# 09-WIFI.net
KiCad netlist of a schematic drawn in Altium Designer
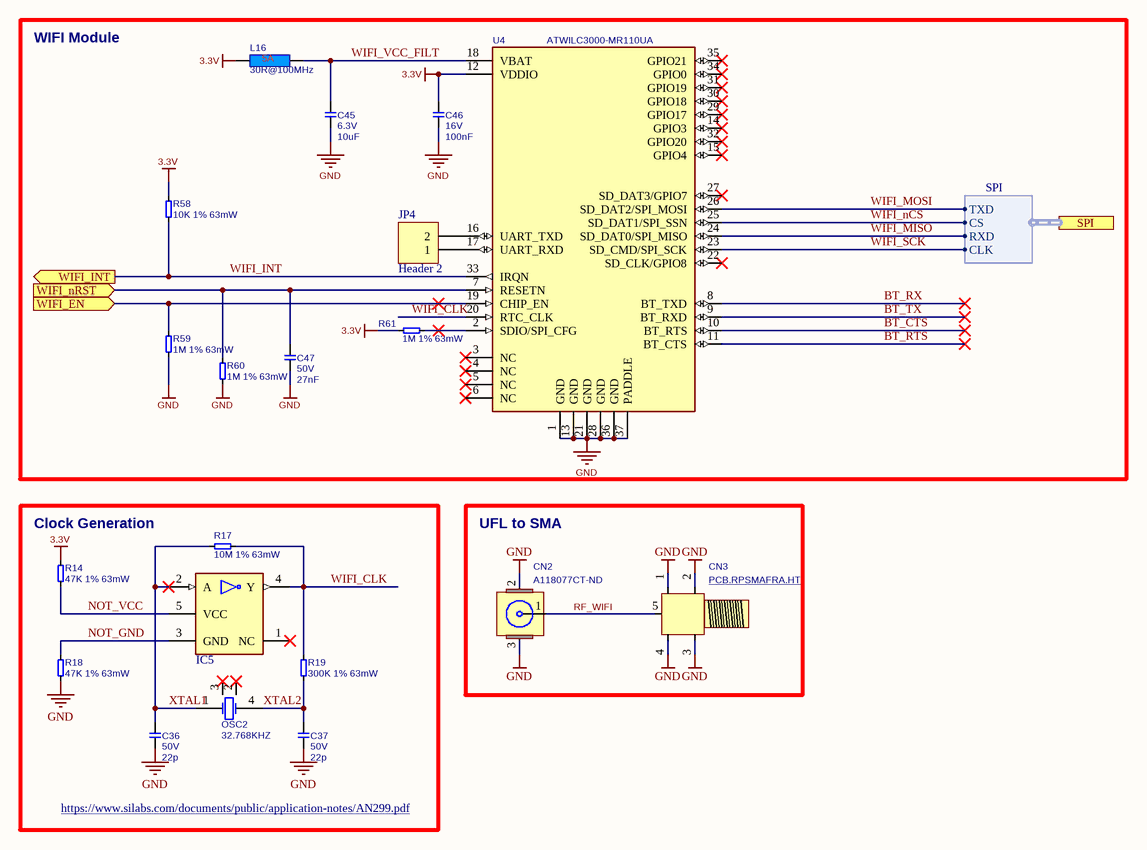
[diagram p0: 09-WIFI.SchDoc]

(export (version "E")
  (design (tool "Eeschema 10.0.6"))
  (components
    (comp (ref "C36")
      (value "22p")
      (footprint "T_CAPC0603X33N")
      (description "Capacitor Ceramic C0G 22pF 50V 10% 0603")
      (fields
        (field (name "TOLERANCE") "10%")
        (field (name "RATING") "50V")
        (field (name "Comment") "22pF 50V 10% C0G")
      )
      (libsource (lib "AI Gateway - Carrier") (part "C-22pF-50V-10%-0603"))
    )
    (comp (ref "C37")
      (value "22p")
      (footprint "T_CAPC0603X33N")
      (description "Capacitor Ceramic C0G 22pF 50V 10% 0603")
      (fields
        (field (name "TOLERANCE") "10%")
        (field (name "RATING") "50V")
        (field (name "Comment") "22pF 50V 10% C0G")
      )
      (libsource (lib "AI Gateway - Carrier") (part "C-22pF-50V-10%-0603"))
    )
    (comp (ref "C45")
      (value "10uF")
      (footprint "T_CAPC0603X33N")
      (description "Capacitor Ceramic X5R 10uF 6.3V 20% 0603")
      (fields
        (field (name "TOLERANCE") "20%")
        (field (name "RATING") "6.3V")
        (field (name "Comment") "10uF 6.3V 20% X5R")
      )
      (libsource (lib "AI Gateway - Carrier") (part "C-10uF-6.3V-20%-0603"))
    )
    (comp (ref "C46")
      (value "100nF")
      (footprint "CAPC1005X60N")
      (description "Capacitor Ceramic X7R 100nF 16V 10% 0603")
      (fields
        (field (name "TOLERANCE") "10%")
        (field (name "RATING") "16V")
        (field (name "Comment") "100nF 16V 10% X7R")
      )
      (libsource (lib "AI Gateway - Carrier") (part "C-100nF-16V-10%-0603"))
    )
    (comp (ref "C47")
      (value "27nF")
      (footprint "T_CAPC0603X33N")
      (description "Capacitor Ceramic X7R 27nF 50V 10% 0603")
      (fields
        (field (name "TOLERANCE") "10%")
        (field (name "RATING") "50V")
        (field (name "Comment") "27nF 50V 20% X7R")
      )
      (libsource (lib "AI Gateway - Carrier") (part "C-27nF-50V-10%-0603"))
    )
    (comp (ref "CN2")
      (value "A118077CT-ND")
      (footprint "U.FL-R-SMT-1")
      (description "U.FL (UMCC) Connector Jack, Male Pin 50Ohm Surface Mount Solder")
      (fields
        (field (name "MFG") "TE Connectivity AMP Connectors")
        (field (name "FOOTPRINT CHECKED") "Assign OK, Footprint OK")
      )
      (libsource (lib "Connectors") (part "CON-TE-A118077CT-ND"))
    )
    (comp (ref "CN3")
      (value "PCB.RPSMAFRA.HT")
      (footprint "0733910320")
      (description "RP-SMA Conector Jack, clavija macho 50Ohm Orificio pasante, ángulo recto Soldadura")
      (fields
        (field (name "MFG") "Taoglas Limited")
        (field (name "FOOTPRINT CHECKED") "Assign OK, Footprint OK")
      )
      (libsource (lib "Connectors") (part "CON-Taoglas-PCB.RPSMAFRA.HT"))
    )
    (comp (ref "IC5")
      (value "SN74LVC1G04")
      (footprint "SOT65P210X110-5N")
      (description "IC INVERTER 1CH 1-INP SC70-5")
      (fields (field (name "MFG") "Texas Instruments"))
      (libsource (lib "AIGateway") (part "IC-TI-SN74LVC1G04"))
    )
    (comp (ref "JP4")
      (value "Header 2")
      (footprint "HDR1X2")
      (description "Header, 2-Pin")
      (fields (field (name "PUBLISHER") "Altium Limited"))
      (libsource (lib "Miscellaneous Connectors") (part "Header 2"))
    )
    (comp (ref "L16")
      (value "30R@100MHz")
      (footprint "INDC1608X95N")
      (description "30 Ohms @ 100MHz 1 Power Line Ferrite Bead 0603 (1608 Metric) 5A 10mOhm")
      (fields
        (field (name "TOLERANCE") "25%")
        (field (name "MFG") "EXC-ML20A390U")
        (field (name "FOOTPRINT CHECKED") "Ok, Assign Ok")
      )
      (libsource (lib "Passive") (part "L-Murata-30R@100MHz-5A-0603"))
    )
    (comp (ref "OSC2")
      (value "32.768KHZ")
      (footprint "OSC_ABRACON_ABS25")
      (description "32.768kHz ±20ppm Cristal 12.5pF  4-SOJ, 5.50mm step")
      (fields (field (name "TOLERANCE") "20ppm") (field (name "MFG") "ABRACON"))
      (libsource (lib "Passive") (part "OSC-ABS25-32.768KHZ-T"))
    )
    (comp (ref "R14")
      (value "47K 1% 63mW")
      (footprint "RESC1005X40N")
      (description "Resistor 47Kohm 63mW 1% 0402")
      (fields (field (name "POWER") "63mW") (field (name "TOLERANCE") "1%"))
      (libsource (lib "AI Gateway - Carrier") (part "R-47K-1%-0402"))
    )
    (comp (ref "R17")
      (value "10M 1% 63mW")
      (footprint "RESC1005X40N")
      (description "Resistor 10Mohm 63mW 1% 0402")
      (fields (field (name "POWER") "63mW") (field (name "TOLERANCE") "1%"))
      (libsource (lib "AI Gateway - Carrier") (part "R-10M-1%-0402"))
    )
    (comp (ref "R18")
      (value "47K 1% 63mW")
      (footprint "RESC1005X40N")
      (description "Resistor 47Kohm 63mW 1% 0402")
      (fields (field (name "POWER") "63mW") (field (name "TOLERANCE") "1%"))
      (libsource (lib "AI Gateway - Carrier") (part "R-47K-1%-0402"))
    )
    (comp (ref "R19")
      (value "300K 1% 63mW")
      (footprint "RESC1005X40N")
      (description "Resistor 300Kohm 63mW 1% 0402")
      (fields (field (name "POWER") "63mW") (field (name "TOLERANCE") "1%"))
      (libsource (lib "AI Gateway - Carrier") (part "R-300K-1%-0402"))
    )
    (comp (ref "R58")
      (value "10K 1% 63mW")
      (footprint "RESC1005X40N")
      (description "Resistor 10Kohm 63mW 1% 0402")
      (fields (field (name "POWER") "63mW") (field (name "TOLERANCE") "1%"))
      (libsource (lib "AI Gateway - Carrier") (part "R-10K-1%-0402"))
    )
    (comp (ref "R59")
      (value "1M 1% 63mW")
      (footprint "RESC1005X40N")
      (description "Resistor 1Mohm 63mW 1% 0402")
      (fields (field (name "POWER") "63mW") (field (name "TOLERANCE") "1%"))
      (libsource (lib "AI Gateway - Carrier") (part "R-1M-1%-0402"))
    )
    (comp (ref "R60")
      (value "1M 1% 63mW")
      (footprint "RESC1005X40N")
      (description "Resistor 1Mohm 63mW 1% 0402")
      (fields (field (name "POWER") "63mW") (field (name "TOLERANCE") "1%"))
      (libsource (lib "AI Gateway - Carrier") (part "R-1M-1%-0402"))
    )
    (comp (ref "R61")
      (value "1M 1% 63mW")
      (footprint "RESC1005X40N")
      (description "Resistor 1Mohm 63mW 1% 0402")
      (fields (field (name "POWER") "63mW") (field (name "TOLERANCE") "1%"))
      (libsource (lib "AI Gateway - Carrier") (part "R-1M-1%-0402"))
    )
    (comp (ref "U4")
      (value "ATWILC3000-MR110UA")
      (footprint "AIGateway:ATWILC3000-MR110CA")
      (fields (field (name "MFG") "MICROCHIP") (field (name "SYMBOL CHECKED") "M"))
      (libsource (lib "AIGateway") (part "IC-Microchip-ATWILC3000"))
    )
  )
  (nets
    (net (code "2") (name "/BT_CTS") (class "Default")
      (node (ref "U4") (pin "10") (pinfunction "BT_RTS_10") (pintype "bidirectional+no_connect"))
    )
    (net (code "3") (name "/BT_RTS") (class "Default")
      (node (ref "U4") (pin "11") (pinfunction "BT_CTS_11") (pintype "bidirectional+no_connect"))
    )
    (net (code "4") (name "/BT_RX") (class "Default")
      (node (ref "U4") (pin "8") (pinfunction "BT_TXD_8") (pintype "bidirectional+no_connect"))
    )
    (net (code "5") (name "/BT_TX") (class "Default")
      (node (ref "U4") (pin "9") (pinfunction "BT_RXD_9") (pintype "bidirectional+no_connect"))
    )
    (net (code "6") (name "/NOT_GND") (class "Default")
      (node (ref "IC5") (pin "3") (pinfunction "GND_3") (pintype "power_in"))
      (node (ref "R18") (pin "2") (pinfunction "2_2") (pintype "passive"))
    )
    (net (code "7") (name "/NOT_VCC") (class "Default")
      (node (ref "IC5") (pin "5") (pinfunction "VCC_5") (pintype "power_in"))
      (node (ref "R14") (pin "1") (pinfunction "1_1") (pintype "passive"))
    )
    (net (code "8") (name "/RF_WIFI") (class "Default")
      (node (ref "CN2") (pin "1") (pinfunction "SIG_1") (pintype "passive"))
      (node (ref "CN3") (pin "5") (pinfunction "SIG_5") (pintype "passive"))
    )
    (net (code "9") (name "/WIFI_CLK") (class "Default")
      (node (ref "IC5") (pin "4") (pinfunction "Y_4") (pintype "output"))
      (node (ref "R17") (pin "1") (pinfunction "1_1") (pintype "passive"))
      (node (ref "R19") (pin "2") (pinfunction "2_2") (pintype "passive"))
      (node (ref "U4") (pin "20") (pinfunction "RTC_CLK_20") (pintype "input"))
    )
    (net (code "10") (name "/WIFI_EN") (class "Default")
      (node (ref "R59") (pin "2") (pinfunction "2_2") (pintype "passive"))
      (node (ref "U4") (pin "19") (pinfunction "CHIP_EN_19") (pintype "input"))
    )
    (net (code "11") (name "/WIFI_INT") (class "Default")
      (node (ref "R58") (pin "1") (pinfunction "1_1") (pintype "passive"))
      (node (ref "U4") (pin "33") (pinfunction "IRQN_33") (pintype "output"))
    )
    (net (code "12") (name "/WIFI_MISO") (class "Default")
      (node (ref "U4") (pin "24") (pinfunction "SD_DAT0/SPI_MISO_24") (pintype "bidirectional"))
    )
    (net (code "13") (name "/WIFI_MOSI") (class "Default")
      (node (ref "U4") (pin "26") (pinfunction "SD_DAT2/SPI_MOSI_26") (pintype "bidirectional"))
    )
    (net (code "14") (name "/WIFI_SCK") (class "Default")
      (node (ref "U4") (pin "23") (pinfunction "SD_CMD/SPI_SCK_23") (pintype "bidirectional"))
    )
    (net (code "15") (name "/WIFI_VCC_FILT") (class "Default")
      (node (ref "C45") (pin "2") (pinfunction "2_2") (pintype "passive"))
      (node (ref "L16") (pin "1") (pinfunction "1_1") (pintype "passive"))
      (node (ref "U4") (pin "18") (pinfunction "VBAT_18") (pintype "power_in"))
    )
    (net (code "16") (name "/WIFI_nCS") (class "Default")
      (node (ref "U4") (pin "25") (pinfunction "SD_DAT1/SPI_SSN_25") (pintype "bidirectional"))
    )
    (net (code "17") (name "/WIFI_nRST") (class "Default")
      (node (ref "C47") (pin "2") (pinfunction "2_2") (pintype "passive"))
      (node (ref "R60") (pin "2") (pinfunction "2_2") (pintype "passive"))
      (node (ref "U4") (pin "7") (pinfunction "RESETN_7") (pintype "input"))
    )
    (net (code "18") (name "/XTAL1") (class "Default")
      (node (ref "C36") (pin "2") (pinfunction "2_2") (pintype "passive"))
      (node (ref "IC5") (pin "2") (pinfunction "A_2") (pintype "input"))
      (node (ref "OSC2") (pin "1") (pinfunction "OSC1_1") (pintype "passive"))
      (node (ref "R17") (pin "2") (pinfunction "2_2") (pintype "passive"))
    )
    (net (code "19") (name "/XTAL2") (class "Default")
      (node (ref "C37") (pin "2") (pinfunction "2_2") (pintype "passive"))
      (node (ref "OSC2") (pin "4") (pinfunction "OSC4_4") (pintype "passive"))
      (node (ref "R19") (pin "1") (pinfunction "1_1") (pintype "passive"))
    )
    (net (code "21") (name "3.3V") (class "Default")
      (node (ref "C46") (pin "2") (pinfunction "2_2") (pintype "passive"))
      (node (ref "L16") (pin "2") (pinfunction "2_2") (pintype "passive"))
      (node (ref "R14") (pin "2") (pinfunction "2_2") (pintype "passive"))
      (node (ref "R58") (pin "2") (pinfunction "2_2") (pintype "passive"))
      (node (ref "R61") (pin "1") (pinfunction "1_1") (pintype "passive"))
      (node (ref "U4") (pin "12") (pinfunction "VDDIO_12") (pintype "power_in"))
    )
    (net (code "22") (name "GND") (class "Default")
      (node (ref "C36") (pin "1") (pinfunction "1_1") (pintype "passive"))
      (node (ref "C37") (pin "1") (pinfunction "1_1") (pintype "passive"))
      (node (ref "C45") (pin "1") (pinfunction "1_1") (pintype "passive"))
      (node (ref "C46") (pin "1") (pinfunction "1_1") (pintype "passive"))
      (node (ref "C47") (pin "1") (pinfunction "1_1") (pintype "passive"))
      (node (ref "CN2") (pin "2") (pinfunction "GND_2") (pintype "passive"))
      (node (ref "CN2") (pin "3") (pinfunction "GND_3") (pintype "passive"))
      (node (ref "CN3") (pin "1") (pinfunction "GND_1") (pintype "passive"))
      (node (ref "CN3") (pin "2") (pinfunction "GND_2") (pintype "passive"))
      (node (ref "CN3") (pin "3") (pinfunction "GND_3") (pintype "passive"))
      (node (ref "CN3") (pin "4") (pinfunction "GND_4") (pintype "passive"))
      (node (ref "R18") (pin "1") (pinfunction "1_1") (pintype "passive"))
      (node (ref "R59") (pin "1") (pinfunction "1_1") (pintype "passive"))
      (node (ref "R60") (pin "1") (pinfunction "1_1") (pintype "passive"))
      (node (ref "U4") (pin "1") (pinfunction "GND_1") (pintype "power_in"))
      (node (ref "U4") (pin "13") (pinfunction "GND_13") (pintype "power_in"))
      (node (ref "U4") (pin "21") (pinfunction "GND_21") (pintype "power_in"))
      (node (ref "U4") (pin "28") (pinfunction "GND_28") (pintype "power_in"))
      (node (ref "U4") (pin "36") (pinfunction "GND_36") (pintype "power_in"))
      (node (ref "U4") (pin "37") (pinfunction "PADDLE_37") (pintype "power_in"))
    )
    (net (code "23") (name "Net-(U4-SDIO{slash}SPI_CFG)") (class "Default")
      (node (ref "R61") (pin "2") (pinfunction "2_2") (pintype "passive"))
      (node (ref "U4") (pin "2") (pinfunction "SDIO/SPI_CFG_2") (pintype "input"))
    )
    (net (code "24") (name "Net-(U4-UART_RXD)") (class "Default")
      (node (ref "JP4") (pin "1") (pinfunction "1_1") (pintype "passive"))
      (node (ref "U4") (pin "17") (pinfunction "UART_RXD_17") (pintype "bidirectional"))
    )
    (net (code "25") (name "Net-(U4-UART_TXD)") (class "Default")
      (node (ref "JP4") (pin "2") (pinfunction "2_2") (pintype "passive"))
      (node (ref "U4") (pin "16") (pinfunction "UART_TXD_16") (pintype "bidirectional"))
    )
    (net (code "26") (name "unconnected-(IC5-NC-Pad1)") (class "Default")
      (node (ref "IC5") (pin "1") (pinfunction "NC_1") (pintype "passive+no_connect"))
    )
    (net (code "27") (name "unconnected-(OSC2-Pad2)") (class "Default")
      (node (ref "OSC2") (pin "2") (pinfunction "2_2") (pintype "passive+no_connect"))
    )
    (net (code "28") (name "unconnected-(OSC2-Pad3)") (class "Default")
      (node (ref "OSC2") (pin "3") (pinfunction "3_3") (pintype "passive+no_connect"))
    )
    (net (code "29") (name "unconnected-(U4-GPIO0-Pad34)") (class "Default")
      (node (ref "U4") (pin "34") (pinfunction "GPIO0_34") (pintype "bidirectional+no_connect"))
    )
    (net (code "30") (name "unconnected-(U4-GPIO3-Pad14)") (class "Default")
      (node (ref "U4") (pin "14") (pinfunction "GPIO3_14") (pintype "bidirectional+no_connect"))
    )
    (net (code "31") (name "unconnected-(U4-GPIO4-Pad15)") (class "Default")
      (node (ref "U4") (pin "15") (pinfunction "GPIO4_15") (pintype "bidirectional+no_connect"))
    )
    (net (code "32") (name "unconnected-(U4-GPIO17-Pad29)") (class "Default")
      (node (ref "U4") (pin "29") (pinfunction "GPIO17_29") (pintype "bidirectional+no_connect"))
    )
    (net (code "33") (name "unconnected-(U4-GPIO18-Pad30)") (class "Default")
      (node (ref "U4") (pin "30") (pinfunction "GPIO18_30") (pintype "bidirectional+no_connect"))
    )
    (net (code "34") (name "unconnected-(U4-GPIO19-Pad31)") (class "Default")
      (node (ref "U4") (pin "31") (pinfunction "GPIO19_31") (pintype "bidirectional+no_connect"))
    )
    (net (code "35") (name "unconnected-(U4-GPIO20-Pad32)") (class "Default")
      (node (ref "U4") (pin "32") (pinfunction "GPIO20_32") (pintype "bidirectional+no_connect"))
    )
    (net (code "36") (name "unconnected-(U4-GPIO21-Pad35)") (class "Default")
      (node (ref "U4") (pin "35") (pinfunction "GPIO21_35") (pintype "bidirectional+no_connect"))
    )
    (net (code "37") (name "unconnected-(U4-NC-Pad3)") (class "Default")
      (node (ref "U4") (pin "3") (pinfunction "NC_3") (pintype "passive+no_connect"))
    )
    (net (code "38") (name "unconnected-(U4-NC-Pad4)") (class "Default")
      (node (ref "U4") (pin "4") (pinfunction "NC_4") (pintype "passive+no_connect"))
    )
    (net (code "39") (name "unconnected-(U4-NC-Pad5)") (class "Default")
      (node (ref "U4") (pin "5") (pinfunction "NC_5") (pintype "passive+no_connect"))
    )
    (net (code "40") (name "unconnected-(U4-NC-Pad6)") (class "Default")
      (node (ref "U4") (pin "6") (pinfunction "NC_6") (pintype "passive+no_connect"))
    )
    (net (code "41") (name "unconnected-(U4-SD_CLK{slash}GPIO8-Pad22)") (class "Default")
      (node (ref "U4") (pin "22") (pinfunction "SD_CLK/GPIO8_22") (pintype "bidirectional+no_connect"))
    )
    (net (code "42") (name "unconnected-(U4-SD_DAT3{slash}GPIO7-Pad27)") (class "Default")
      (node (ref "U4") (pin "27") (pinfunction "SD_DAT3/GPIO7_27") (pintype "bidirectional+no_connect"))
    )
  )
)
